# CC1101_revc.net
KiCad netlist of a schematic drawn in EAGLE
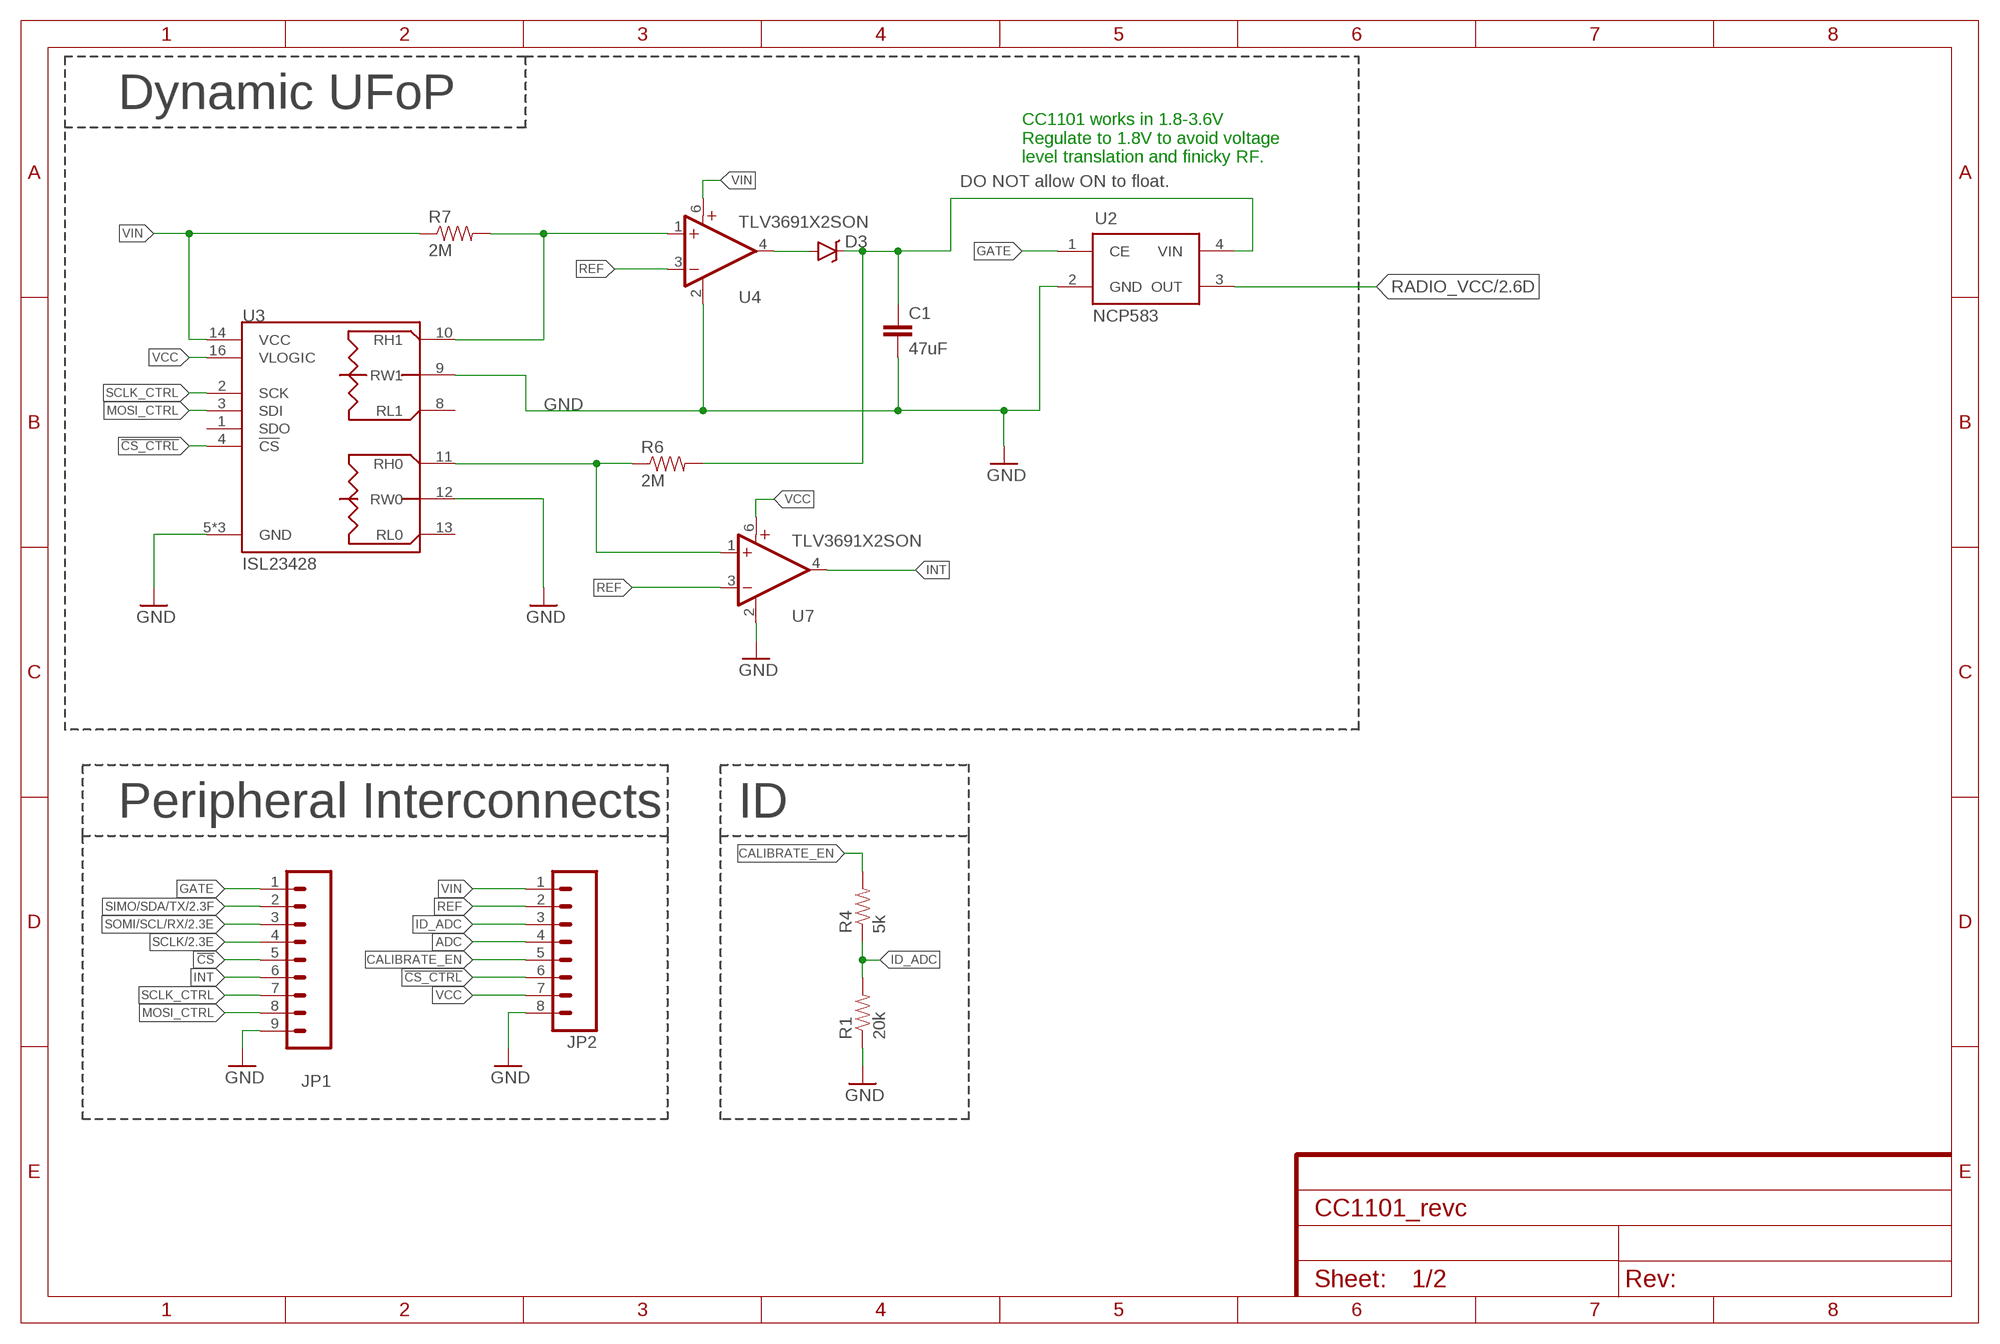
[diagram p0: schematic, sheet 1]
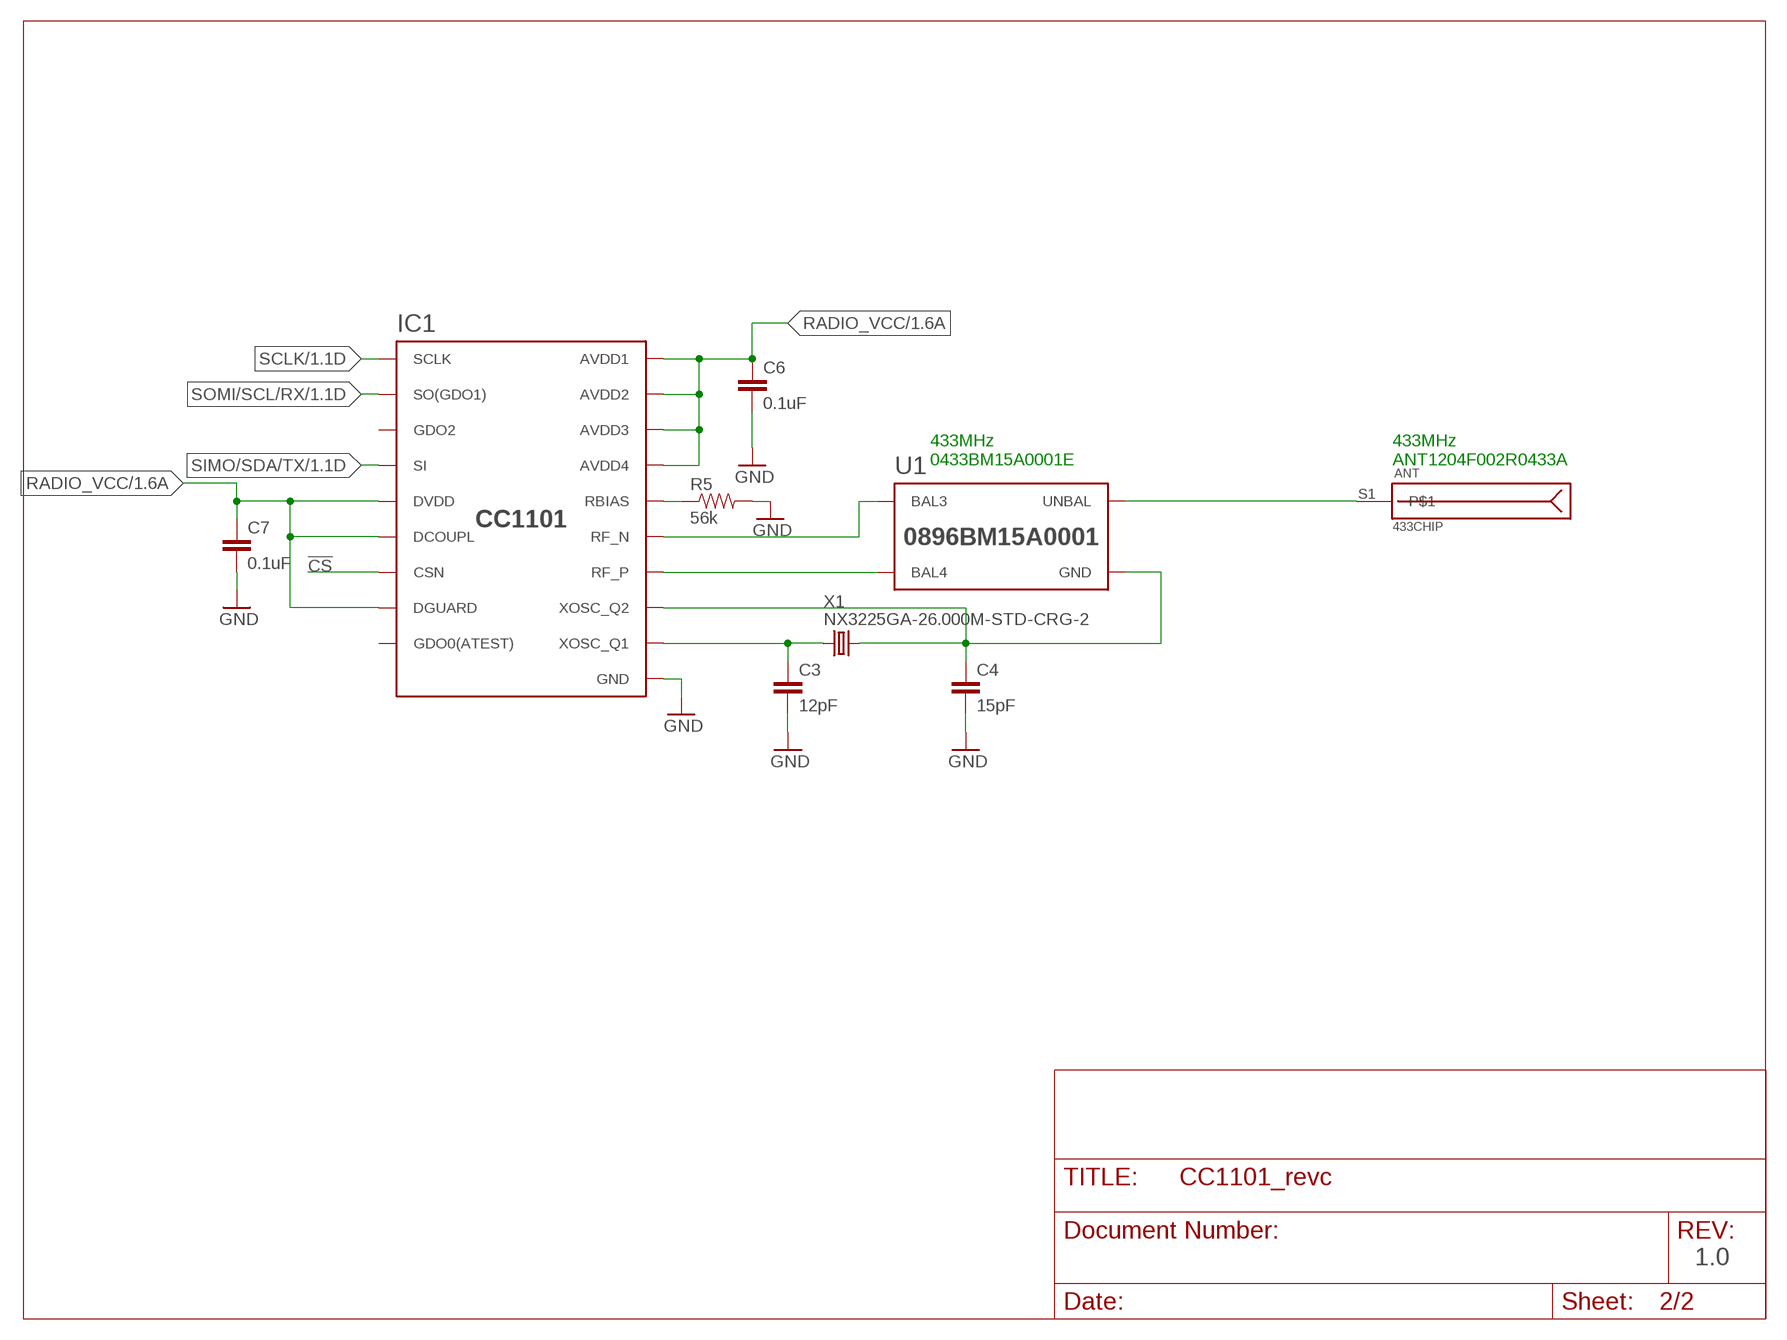
[diagram p1: schematic, sheet 2]

(export (version "E")
  (design (tool "Eeschema 10.0.6"))
  (components
    (comp (ref "C1")
      (value "47uF")
      (footprint "eagle-import:1206")
      (fields (field (name "MPN") "GRM31CR60J476ME19L"))
      (libsource (lib "eagle-import") (part "CAP1206"))
    )
    (comp (ref "D3")
      (value "RB751")
      (footprint "eagle-import:SOD-523")
      (fields (field (name "MPN") "RB751S40T1G"))
      (libsource (lib "eagle-import") (part "DIODE-SCHOTTKY-RB751"))
    )
    (comp (ref "JP1")
      (value "M091.27MM")
      (footprint "eagle-import:1X09-1.27MM")
      (fields (field (name "MPN") "GRPB091VWVN-RC "))
      (libsource (lib "eagle-import") (part "M091.27MM"))
    )
    (comp (ref "JP2")
      (value "M081.27MM")
      (footprint "eagle-import:1X08-1.27MM")
      (fields (field (name "MPN") "GRPB081VWVN-RC "))
      (libsource (lib "eagle-import") (part "M081.27MM"))
    )
    (comp (ref "R1")
      (value "20k")
      (footprint "eagle-import:0402")
      (fields (field (name "MPN") "ERJ-2RKF2002X"))
      (libsource (lib "eagle-import") (part "R-EU"))
    )
    (comp (ref "R4")
      (value "5k")
      (footprint "eagle-import:0402")
      (fields (field (name "MPN") "ERJ-2RKF4991X"))
      (libsource (lib "eagle-import") (part "R-EU"))
    )
    (comp (ref "R6")
      (value "2M")
      (footprint "eagle-import:0402")
      (fields (field (name "MPN") "RC1005F205CS"))
      (libsource (lib "eagle-import") (part "R-EU"))
    )
    (comp (ref "R7")
      (value "2M")
      (footprint "eagle-import:0402")
      (fields (field (name "MPN") "RC1005F205CS"))
      (libsource (lib "eagle-import") (part "R-EU"))
    )
    (comp (ref "U2")
      (value "NCP583")
      (footprint "eagle-import:SC82-AB_1PRIMARY")
      (fields (field (name "MPN") "NCP583SQ18T1G"))
      (libsource (lib "eagle-import") (part "NCP583"))
    )
    (comp (ref "U3")
      (value "ISL23428")
      (footprint "eagle-import:UTQFN-16")
      (fields (field (name "MPN") "ISL23428TFRUZ-T7A"))
      (libsource (lib "eagle-import") (part "ISL23428"))
    )
    (comp (ref "U4")
      (value "TLV3691X2SON")
      (footprint "eagle-import:X2SON")
      (fields (field (name "MPN") "TLV3691IDPFR"))
      (libsource (lib "eagle-import") (part "TLV3691X2SON"))
    )
    (comp (ref "U7")
      (value "TLV3691X2SON")
      (footprint "eagle-import:X2SON")
      (fields (field (name "MPN") "TLV3691IDPFR"))
      (libsource (lib "eagle-import") (part "TLV3691X2SON"))
    )
    (comp (ref "ANT")
      (value "433CHIP")
      (footprint "eagle-import:ANT-433-USP")
      (fields (field (name "MPN") "ANT1204F002R0433A"))
      (libsource (lib "eagle-import") (part "433CHIP"))
    )
    (comp (ref "C3")
      (value "12pF")
      (footprint "eagle-import:0603")
      (fields (field (name "MPN") "06035A120FAT2A"))
      (libsource (lib "eagle-import") (part "C-EU0603"))
    )
    (comp (ref "C4")
      (value "15pF")
      (footprint "eagle-import:0603")
      (fields (field (name "MPN") "C1608C0G1H150J080AA"))
      (libsource (lib "eagle-import") (part "C-EU0603"))
    )
    (comp (ref "C6")
      (value "0.1uF")
      (footprint "eagle-import:0603")
      (fields (field (name "MPN") "GCJ188R71H104KA12D"))
      (libsource (lib "eagle-import") (part "C-EU0603"))
    )
    (comp (ref "C7")
      (value "0.1uF")
      (footprint "eagle-import:0603")
      (fields (field (name "MPN") "GCJ188R71H104KA12D"))
      (libsource (lib "eagle-import") (part "C-EU0603"))
    )
    (comp (ref "IC1")
      (value "CC1101")
      (footprint "eagle-import:QLP20")
      (fields (field (name "MPN") "CC1101RGP"))
      (libsource (lib "eagle-import") (part "CC1101"))
    )
    (comp (ref "R5")
      (value "56k")
      (footprint "eagle-import:0603")
      (fields (field (name "MPN") "ERJ-3GEYJ563V"))
      (libsource (lib "eagle-import") (part "R-EU0603"))
    )
    (comp (ref "U1")
      (value "0896BM15A0001")
      (footprint "eagle-import:0896BM15A0001")
      (fields (field (name "MPN") "0433BM15A0001E"))
      (libsource (lib "eagle-import") (part "0896BM15A0001"))
    )
    (comp (ref "X1")
      (value "NX3225GA-26.000M-STD-CRG-2")
      (footprint "eagle-import:XTAL-3.2X2.5")
      (libsource (lib "eagle-import") (part "XTAL-3.2X2.5"))
    )
  )
  (nets
    (net (code "1") (name "ADC") (class "Default")
      (node (ref "JP2") (pin "4") (pinfunction "4_4") (pintype "passive"))
    )
    (net (code "2") (name "CALIBRATE_EN") (class "Default")
      (node (ref "JP2") (pin "5") (pinfunction "5_5") (pintype "passive"))
      (node (ref "R4") (pin "2") (pinfunction "2_2") (pintype "passive"))
    )
    (net (code "3") (name "GATE") (class "Default")
      (node (ref "JP1") (pin "1") (pinfunction "1_1") (pintype "passive"))
      (node (ref "U2") (pin "1") (pinfunction "CE_1") (pintype "bidirectional"))
    )
    (net (code "4") (name "GND") (class "Default")
      (node (ref "C1") (pin "2") (pinfunction "2_2") (pintype "passive"))
      (node (ref "C3") (pin "2") (pinfunction "2_2") (pintype "passive"))
      (node (ref "C4") (pin "2") (pinfunction "2_2") (pintype "passive"))
      (node (ref "C6") (pin "2") (pinfunction "2_2") (pintype "passive"))
      (node (ref "C7") (pin "2") (pinfunction "2_2") (pintype "passive"))
      (node (ref "IC1") (pin "16") (pinfunction "GND_16") (pintype "bidirectional"))
      (node (ref "IC1") (pin "19") (pinfunction "GND_19") (pintype "bidirectional"))
      (node (ref "IC1") (pin "GND") (pinfunction "GND_GND") (pintype "bidirectional"))
      (node (ref "JP1") (pin "9") (pinfunction "9_9") (pintype "passive"))
      (node (ref "JP2") (pin "8") (pinfunction "8_8") (pintype "passive"))
      (node (ref "R1") (pin "1") (pinfunction "1_1") (pintype "passive"))
      (node (ref "R5") (pin "2") (pinfunction "2_2") (pintype "passive"))
      (node (ref "U2") (pin "2") (pinfunction "GND_2") (pintype "bidirectional"))
      (node (ref "U3") (pin "12") (pinfunction "RW0_12") (pintype "bidirectional"))
      (node (ref "U3") (pin "15") (pinfunction "GND_15") (pintype "bidirectional"))
      (node (ref "U3") (pin "5") (pinfunction "GND_5") (pintype "bidirectional"))
      (node (ref "U3") (pin "6") (pinfunction "GND_6") (pintype "bidirectional"))
      (node (ref "U3") (pin "9") (pinfunction "RW1_9") (pintype "bidirectional"))
      (node (ref "U4") (pin "2") (pinfunction "GND_2") (pintype "power_in"))
      (node (ref "U7") (pin "2") (pinfunction "GND_2") (pintype "power_in"))
    )
    (net (code "5") (name "ID_ADC") (class "Default")
      (node (ref "JP2") (pin "3") (pinfunction "3_3") (pintype "passive"))
      (node (ref "R1") (pin "2") (pinfunction "2_2") (pintype "passive"))
      (node (ref "R4") (pin "1") (pinfunction "1_1") (pintype "passive"))
    )
    (net (code "6") (name "INT") (class "Default")
      (node (ref "JP1") (pin "6") (pinfunction "6_6") (pintype "passive"))
      (node (ref "U7") (pin "4") (pinfunction "OUT_4") (pintype "output"))
    )
    (net (code "7") (name "MOSI_CTRL") (class "Default")
      (node (ref "JP1") (pin "8") (pinfunction "8_8") (pintype "passive"))
      (node (ref "U3") (pin "3") (pinfunction "SDI_3") (pintype "bidirectional"))
    )
    (net (code "8") (name "Net-(ANT-P$1)") (class "Default")
      (node (ref "ANT") (pin "S1") (pinfunction "P$1_S1") (pintype "bidirectional"))
      (node (ref "U1") (pin "1") (pinfunction "UNBAL_1") (pintype "bidirectional"))
    )
    (net (code "9") (name "Net-(IC1-RBIAS)") (class "Default")
      (node (ref "IC1") (pin "17") (pinfunction "RBIAS_17") (pintype "bidirectional"))
      (node (ref "R5") (pin "1") (pinfunction "1_1") (pintype "passive"))
    )
    (net (code "10") (name "Net-(IC1-RF_N)") (class "Default")
      (node (ref "IC1") (pin "13") (pinfunction "RF_N_13") (pintype "bidirectional"))
      (node (ref "U1") (pin "3") (pinfunction "BAL3_3") (pintype "bidirectional"))
    )
    (net (code "11") (name "Net-(IC1-RF_P)") (class "Default")
      (node (ref "IC1") (pin "12") (pinfunction "RF_P_12") (pintype "bidirectional"))
      (node (ref "U1") (pin "4") (pinfunction "BAL4_4") (pintype "bidirectional"))
    )
    (net (code "12") (name "Net-(IC1-XOSC_Q1)") (class "Default")
      (node (ref "C3") (pin "1") (pinfunction "1_1") (pintype "passive"))
      (node (ref "IC1") (pin "8") (pinfunction "XOSC_Q1_8") (pintype "bidirectional"))
      (node (ref "X1") (pin "1") (pinfunction "1_1") (pintype "passive"))
    )
    (net (code "13") (name "Net-(IC1-XOSC_Q2)") (class "Default")
      (node (ref "C4") (pin "1") (pinfunction "1_1") (pintype "passive"))
      (node (ref "IC1") (pin "10") (pinfunction "XOSC_Q2_10") (pintype "bidirectional"))
      (node (ref "U1") (pin "2") (pinfunction "GND_2") (pintype "bidirectional"))
      (node (ref "U1") (pin "5") (pinfunction "GND_5") (pintype "bidirectional"))
      (node (ref "U1") (pin "6") (pinfunction "GND_6") (pintype "bidirectional"))
      (node (ref "X1") (pin "3") (pinfunction "2_3") (pintype "passive"))
    )
    (net (code "14") (name "Net-(U2-VIN)") (class "Default")
      (node (ref "C1") (pin "1") (pinfunction "1_1") (pintype "passive"))
      (node (ref "D3") (pin "C") (pinfunction "C_C") (pintype "passive"))
      (node (ref "R6") (pin "2") (pinfunction "2_2") (pintype "passive"))
      (node (ref "U2") (pin "4") (pinfunction "VIN_4") (pintype "bidirectional"))
    )
    (net (code "15") (name "Net-(U3-RH0)") (class "Default")
      (node (ref "R6") (pin "1") (pinfunction "1_1") (pintype "passive"))
      (node (ref "U3") (pin "11") (pinfunction "RH0_11") (pintype "bidirectional"))
      (node (ref "U7") (pin "1") (pinfunction "+IN_1") (pintype "input"))
    )
    (net (code "16") (name "Net-(U3-RH1)") (class "Default")
      (node (ref "R7") (pin "2") (pinfunction "2_2") (pintype "passive"))
      (node (ref "U3") (pin "10") (pinfunction "RH1_10") (pintype "bidirectional"))
      (node (ref "U4") (pin "1") (pinfunction "+IN_1") (pintype "input"))
    )
    (net (code "17") (name "Net-(U4-OUT)") (class "Default")
      (node (ref "D3") (pin "A") (pinfunction "A_A") (pintype "passive"))
      (node (ref "U4") (pin "4") (pinfunction "OUT_4") (pintype "output"))
    )
    (net (code "18") (name "RADIO_VCC") (class "Default")
      (node (ref "C6") (pin "1") (pinfunction "1_1") (pintype "passive"))
      (node (ref "C7") (pin "1") (pinfunction "1_1") (pintype "passive"))
      (node (ref "IC1") (pin "11") (pinfunction "AVDD2_11") (pintype "bidirectional"))
      (node (ref "IC1") (pin "14") (pinfunction "AVDD3_14") (pintype "bidirectional"))
      (node (ref "IC1") (pin "15") (pinfunction "AVDD4_15") (pintype "bidirectional"))
      (node (ref "IC1") (pin "18") (pinfunction "DGUARD_18") (pintype "bidirectional"))
      (node (ref "IC1") (pin "4") (pinfunction "DVDD_4") (pintype "bidirectional"))
      (node (ref "IC1") (pin "5") (pinfunction "DCOUPL_5") (pintype "bidirectional"))
      (node (ref "IC1") (pin "9") (pinfunction "AVDD1_9") (pintype "bidirectional"))
      (node (ref "U2") (pin "3") (pinfunction "OUT_3") (pintype "bidirectional"))
    )
    (net (code "19") (name "REF") (class "Default")
      (node (ref "JP2") (pin "2") (pinfunction "2_2") (pintype "passive"))
      (node (ref "U4") (pin "3") (pinfunction "-IN_3") (pintype "input"))
      (node (ref "U7") (pin "3") (pinfunction "-IN_3") (pintype "input"))
    )
    (net (code "20") (name "SCLK") (class "Default")
      (node (ref "IC1") (pin "1") (pinfunction "SCLK_1") (pintype "bidirectional"))
      (node (ref "JP1") (pin "4") (pinfunction "4_4") (pintype "passive"))
    )
    (net (code "21") (name "SCLK_CTRL") (class "Default")
      (node (ref "JP1") (pin "7") (pinfunction "7_7") (pintype "passive"))
      (node (ref "U3") (pin "2") (pinfunction "SCK_2") (pintype "bidirectional"))
    )
    (net (code "22") (name "SIMO{slash}SDA{slash}TX") (class "Default")
      (node (ref "IC1") (pin "20") (pinfunction "SI_20") (pintype "bidirectional"))
      (node (ref "JP1") (pin "2") (pinfunction "2_2") (pintype "passive"))
    )
    (net (code "23") (name "SOMI{slash}SCL{slash}RX") (class "Default")
      (node (ref "IC1") (pin "2") (pinfunction "SO(GDO1)_2") (pintype "bidirectional"))
      (node (ref "JP1") (pin "3") (pinfunction "3_3") (pintype "passive"))
    )
    (net (code "24") (name "VCC") (class "Default")
      (node (ref "JP2") (pin "7") (pinfunction "7_7") (pintype "passive"))
      (node (ref "U3") (pin "16") (pinfunction "VLOGIC_16") (pintype "bidirectional"))
      (node (ref "U7") (pin "6") (pinfunction "V+_6") (pintype "power_in"))
    )
    (net (code "25") (name "VIN") (class "Default")
      (node (ref "JP2") (pin "1") (pinfunction "1_1") (pintype "passive"))
      (node (ref "R7") (pin "1") (pinfunction "1_1") (pintype "passive"))
      (node (ref "U3") (pin "14") (pinfunction "VCC_14") (pintype "bidirectional"))
      (node (ref "U4") (pin "6") (pinfunction "V+_6") (pintype "power_in"))
    )
    (net (code "26") (name "unconnected-(IC1-GDO0(ATEST)-Pad6)") (class "Default")
      (node (ref "IC1") (pin "6") (pinfunction "GDO0(ATEST)_6") (pintype "bidirectional"))
    )
    (net (code "27") (name "unconnected-(IC1-GDO2-Pad3)") (class "Default")
      (node (ref "IC1") (pin "3") (pinfunction "GDO2_3") (pintype "bidirectional"))
    )
    (net (code "28") (name "unconnected-(U3-RL0-Pad13)") (class "Default")
      (node (ref "U3") (pin "13") (pinfunction "RL0_13") (pintype "bidirectional"))
    )
    (net (code "29") (name "unconnected-(U3-RL1-Pad8)") (class "Default")
      (node (ref "U3") (pin "8") (pinfunction "RL1_8") (pintype "bidirectional"))
    )
    (net (code "30") (name "unconnected-(U3-SDO-Pad1)") (class "Default")
      (node (ref "U3") (pin "1") (pinfunction "SDO_1") (pintype "bidirectional"))
    )
    (net (code "31") (name "~{CS_CTRL}") (class "Default")
      (node (ref "JP2") (pin "6") (pinfunction "6_6") (pintype "passive"))
      (node (ref "U3") (pin "4") (pinfunction "~{CS}_4") (pintype "bidirectional"))
    )
    (net (code "32") (name "~{CS}") (class "Default")
      (node (ref "IC1") (pin "7") (pinfunction "CSN_7") (pintype "bidirectional"))
      (node (ref "JP1") (pin "5") (pinfunction "5_5") (pintype "passive"))
    )
  )
)
